# LVBarGraphDriver.net
KiCad netlist of a schematic drawn in EAGLE
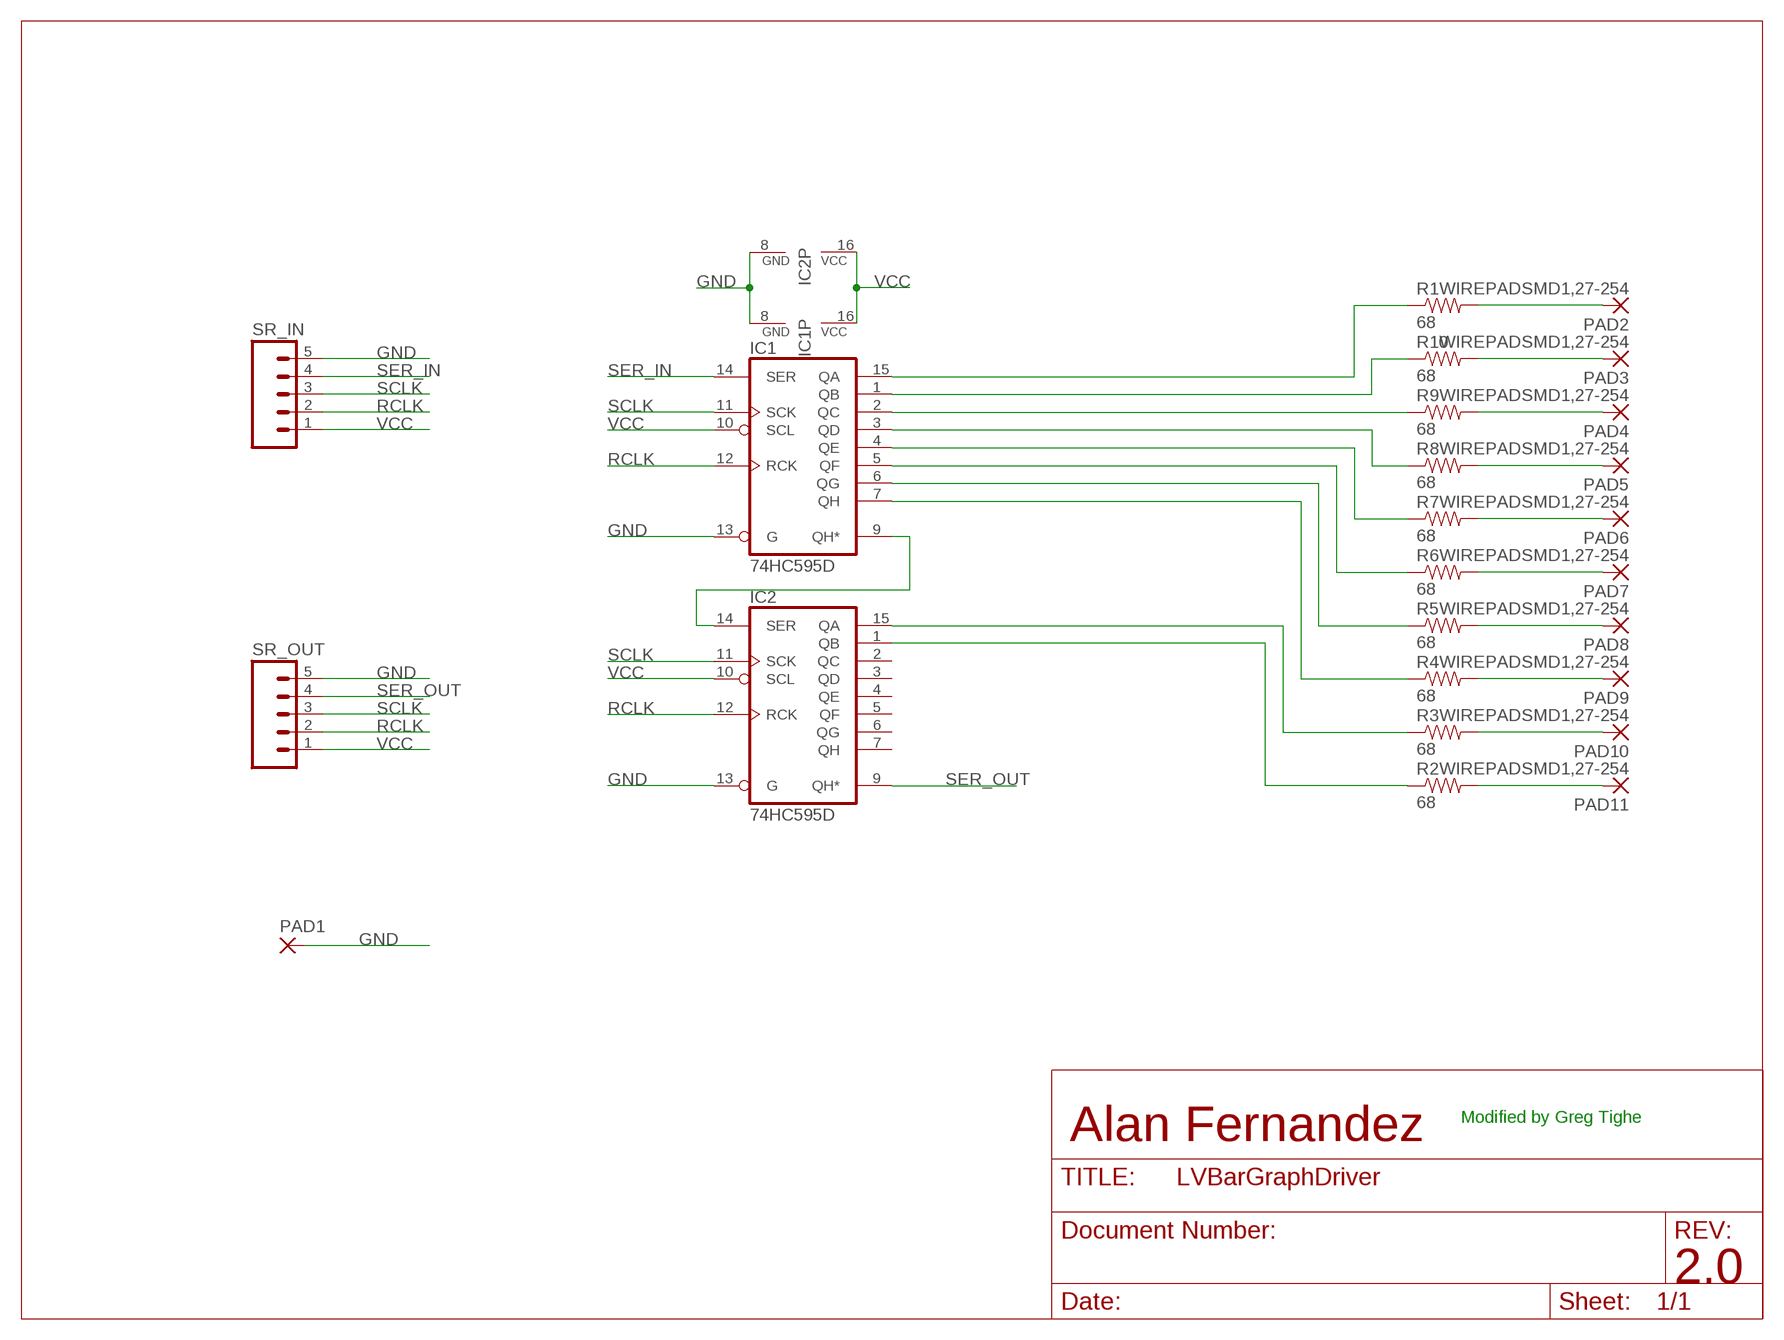
[diagram p0: schematic, sheet 1]

(export (version "E")
  (design (tool "Eeschema 10.0.6"))
  (components
    (comp (ref "IC1")
      (value "74HC595D")
      (footprint "eagle-import:SO16")
      (libsource (lib "eagle-import") (part "74595DHC"))
    )
    (comp (ref "IC2")
      (value "74HC595D")
      (footprint "eagle-import:SO16")
      (libsource (lib "eagle-import") (part "74595DHC"))
    )
    (comp (ref "PAD1")
      (value "SMD2")
      (footprint "eagle-import:SMD1,27-2,54")
      (libsource (lib "eagle-import") (part "SMD2"))
    )
    (comp (ref "PAD2")
      (value "WIREPADSMD1,27-254")
      (footprint "eagle-import:SMD1,27-2,54")
      (libsource (lib "eagle-import") (part "WIREPADSMD1,27-254"))
    )
    (comp (ref "PAD3")
      (value "WIREPADSMD1,27-254")
      (footprint "eagle-import:SMD1,27-2,54")
      (libsource (lib "eagle-import") (part "WIREPADSMD1,27-254"))
    )
    (comp (ref "PAD4")
      (value "WIREPADSMD1,27-254")
      (footprint "eagle-import:SMD1,27-2,54")
      (libsource (lib "eagle-import") (part "WIREPADSMD1,27-254"))
    )
    (comp (ref "PAD5")
      (value "WIREPADSMD1,27-254")
      (footprint "eagle-import:SMD1,27-2,54")
      (libsource (lib "eagle-import") (part "WIREPADSMD1,27-254"))
    )
    (comp (ref "PAD6")
      (value "WIREPADSMD1,27-254")
      (footprint "eagle-import:SMD1,27-2,54")
      (libsource (lib "eagle-import") (part "WIREPADSMD1,27-254"))
    )
    (comp (ref "PAD7")
      (value "WIREPADSMD1,27-254")
      (footprint "eagle-import:SMD1,27-2,54")
      (libsource (lib "eagle-import") (part "WIREPADSMD1,27-254"))
    )
    (comp (ref "PAD8")
      (value "WIREPADSMD1,27-254")
      (footprint "eagle-import:SMD1,27-2,54")
      (libsource (lib "eagle-import") (part "WIREPADSMD1,27-254"))
    )
    (comp (ref "PAD9")
      (value "WIREPADSMD1,27-254")
      (footprint "eagle-import:SMD1,27-2,54")
      (libsource (lib "eagle-import") (part "WIREPADSMD1,27-254"))
    )
    (comp (ref "PAD10")
      (value "WIREPADSMD1,27-254")
      (footprint "eagle-import:SMD1,27-2,54")
      (libsource (lib "eagle-import") (part "WIREPADSMD1,27-254"))
    )
    (comp (ref "PAD11")
      (value "WIREPADSMD1,27-254")
      (footprint "eagle-import:SMD1,27-2,54")
      (libsource (lib "eagle-import") (part "WIREPADSMD1,27-254"))
    )
    (comp (ref "R1")
      (value "68")
      (footprint "eagle-import:1206")
      (libsource (lib "eagle-import") (part "RESISTOR1206"))
    )
    (comp (ref "R2")
      (value "68")
      (footprint "eagle-import:1206")
      (libsource (lib "eagle-import") (part "RESISTOR1206"))
    )
    (comp (ref "R3")
      (value "68")
      (footprint "eagle-import:1206")
      (libsource (lib "eagle-import") (part "RESISTOR1206"))
    )
    (comp (ref "R4")
      (value "68")
      (footprint "eagle-import:1206")
      (libsource (lib "eagle-import") (part "RESISTOR1206"))
    )
    (comp (ref "R5")
      (value "68")
      (footprint "eagle-import:1206")
      (libsource (lib "eagle-import") (part "RESISTOR1206"))
    )
    (comp (ref "R6")
      (value "68")
      (footprint "eagle-import:1206")
      (libsource (lib "eagle-import") (part "RESISTOR1206"))
    )
    (comp (ref "R7")
      (value "68")
      (footprint "eagle-import:1206")
      (libsource (lib "eagle-import") (part "RESISTOR1206"))
    )
    (comp (ref "R8")
      (value "68")
      (footprint "eagle-import:1206")
      (libsource (lib "eagle-import") (part "RESISTOR1206"))
    )
    (comp (ref "R9")
      (value "68")
      (footprint "eagle-import:1206")
      (libsource (lib "eagle-import") (part "RESISTOR1206"))
    )
    (comp (ref "R10")
      (value "68")
      (footprint "eagle-import:1206")
      (libsource (lib "eagle-import") (part "RESISTOR1206"))
    )
    (comp (ref "SR_IN")
      (value "M05PTH")
      (footprint "eagle-import:1X05")
      (libsource (lib "eagle-import") (part "M05PTH"))
    )
    (comp (ref "SR_OUT")
      (value "M05PTH")
      (footprint "eagle-import:1X05")
      (libsource (lib "eagle-import") (part "M05PTH"))
    )
  )
  (nets
    (net (code "1") (name "/GND") (class "Default")
      (node (ref "IC1") (pin "13") (pinfunction "G_13") (pintype "input"))
      (node (ref "IC1") (pin "8") (pinfunction "GND_8") (pintype "power_in"))
      (node (ref "IC2") (pin "13") (pinfunction "G_13") (pintype "input"))
      (node (ref "IC2") (pin "8") (pinfunction "GND_8") (pintype "power_in"))
      (node (ref "PAD1") (pin "1") (pinfunction "P_1") (pintype "passive"))
      (node (ref "SR_IN") (pin "5") (pinfunction "5_5") (pintype "passive"))
      (node (ref "SR_OUT") (pin "5") (pinfunction "5_5") (pintype "passive"))
    )
    (net (code "2") (name "/RCLK") (class "Default")
      (node (ref "IC1") (pin "12") (pinfunction "RCK_12") (pintype "input"))
      (node (ref "IC2") (pin "12") (pinfunction "RCK_12") (pintype "input"))
      (node (ref "SR_IN") (pin "2") (pinfunction "2_2") (pintype "passive"))
      (node (ref "SR_OUT") (pin "2") (pinfunction "2_2") (pintype "passive"))
    )
    (net (code "3") (name "/SCLK") (class "Default")
      (node (ref "IC1") (pin "11") (pinfunction "SCK_11") (pintype "input"))
      (node (ref "IC2") (pin "11") (pinfunction "SCK_11") (pintype "input"))
      (node (ref "SR_IN") (pin "3") (pinfunction "3_3") (pintype "passive"))
      (node (ref "SR_OUT") (pin "3") (pinfunction "3_3") (pintype "passive"))
    )
    (net (code "4") (name "/SER_IN") (class "Default")
      (node (ref "IC1") (pin "14") (pinfunction "SER_14") (pintype "input"))
      (node (ref "SR_IN") (pin "4") (pinfunction "4_4") (pintype "passive"))
    )
    (net (code "5") (name "/SER_OUT") (class "Default")
      (node (ref "IC2") (pin "9") (pinfunction "QH*_9") (pintype "tri_state"))
      (node (ref "SR_OUT") (pin "4") (pinfunction "4_4") (pintype "passive"))
    )
    (net (code "6") (name "/VCC") (class "Default")
      (node (ref "IC1") (pin "10") (pinfunction "SCL_10") (pintype "input"))
      (node (ref "IC1") (pin "16") (pinfunction "VCC_16") (pintype "power_in"))
      (node (ref "IC2") (pin "10") (pinfunction "SCL_10") (pintype "input"))
      (node (ref "IC2") (pin "16") (pinfunction "VCC_16") (pintype "power_in"))
      (node (ref "SR_IN") (pin "1") (pinfunction "1_1") (pintype "passive"))
      (node (ref "SR_OUT") (pin "1") (pinfunction "1_1") (pintype "passive"))
    )
    (net (code "7") (name "Net-(IC1A-QA)") (class "Default")
      (node (ref "IC1") (pin "15") (pinfunction "QA_15") (pintype "tri_state"))
      (node (ref "R1") (pin "1") (pinfunction "1_1") (pintype "passive"))
    )
    (net (code "8") (name "Net-(IC1A-QB)") (class "Default")
      (node (ref "IC1") (pin "1") (pinfunction "QB_1") (pintype "tri_state"))
      (node (ref "R10") (pin "1") (pinfunction "1_1") (pintype "passive"))
    )
    (net (code "9") (name "Net-(IC1A-QC)") (class "Default")
      (node (ref "IC1") (pin "2") (pinfunction "QC_2") (pintype "tri_state"))
      (node (ref "R9") (pin "1") (pinfunction "1_1") (pintype "passive"))
    )
    (net (code "10") (name "Net-(IC1A-QD)") (class "Default")
      (node (ref "IC1") (pin "3") (pinfunction "QD_3") (pintype "tri_state"))
      (node (ref "R8") (pin "1") (pinfunction "1_1") (pintype "passive"))
    )
    (net (code "11") (name "Net-(IC1A-QE)") (class "Default")
      (node (ref "IC1") (pin "4") (pinfunction "QE_4") (pintype "tri_state"))
      (node (ref "R7") (pin "1") (pinfunction "1_1") (pintype "passive"))
    )
    (net (code "12") (name "Net-(IC1A-QF)") (class "Default")
      (node (ref "IC1") (pin "5") (pinfunction "QF_5") (pintype "tri_state"))
      (node (ref "R6") (pin "1") (pinfunction "1_1") (pintype "passive"))
    )
    (net (code "13") (name "Net-(IC1A-QG)") (class "Default")
      (node (ref "IC1") (pin "6") (pinfunction "QG_6") (pintype "tri_state"))
      (node (ref "R5") (pin "1") (pinfunction "1_1") (pintype "passive"))
    )
    (net (code "14") (name "Net-(IC1A-QH)") (class "Default")
      (node (ref "IC1") (pin "7") (pinfunction "QH_7") (pintype "tri_state"))
      (node (ref "R4") (pin "1") (pinfunction "1_1") (pintype "passive"))
    )
    (net (code "15") (name "Net-(IC1A-QH*)") (class "Default")
      (node (ref "IC1") (pin "9") (pinfunction "QH*_9") (pintype "tri_state"))
      (node (ref "IC2") (pin "14") (pinfunction "SER_14") (pintype "input"))
    )
    (net (code "16") (name "Net-(IC2A-QA)") (class "Default")
      (node (ref "IC2") (pin "15") (pinfunction "QA_15") (pintype "tri_state"))
      (node (ref "R3") (pin "1") (pinfunction "1_1") (pintype "passive"))
    )
    (net (code "17") (name "Net-(IC2A-QB)") (class "Default")
      (node (ref "IC2") (pin "1") (pinfunction "QB_1") (pintype "tri_state"))
      (node (ref "R2") (pin "1") (pinfunction "1_1") (pintype "passive"))
    )
    (net (code "18") (name "Net-(PAD2-P)") (class "Default")
      (node (ref "PAD2") (pin "1") (pinfunction "P_1") (pintype "passive"))
      (node (ref "R1") (pin "2") (pinfunction "2_2") (pintype "passive"))
    )
    (net (code "19") (name "Net-(PAD3-P)") (class "Default")
      (node (ref "PAD3") (pin "1") (pinfunction "P_1") (pintype "passive"))
      (node (ref "R10") (pin "2") (pinfunction "2_2") (pintype "passive"))
    )
    (net (code "20") (name "Net-(PAD4-P)") (class "Default")
      (node (ref "PAD4") (pin "1") (pinfunction "P_1") (pintype "passive"))
      (node (ref "R9") (pin "2") (pinfunction "2_2") (pintype "passive"))
    )
    (net (code "21") (name "Net-(PAD5-P)") (class "Default")
      (node (ref "PAD5") (pin "1") (pinfunction "P_1") (pintype "passive"))
      (node (ref "R8") (pin "2") (pinfunction "2_2") (pintype "passive"))
    )
    (net (code "22") (name "Net-(PAD6-P)") (class "Default")
      (node (ref "PAD6") (pin "1") (pinfunction "P_1") (pintype "passive"))
      (node (ref "R7") (pin "2") (pinfunction "2_2") (pintype "passive"))
    )
    (net (code "23") (name "Net-(PAD7-P)") (class "Default")
      (node (ref "PAD7") (pin "1") (pinfunction "P_1") (pintype "passive"))
      (node (ref "R6") (pin "2") (pinfunction "2_2") (pintype "passive"))
    )
    (net (code "24") (name "Net-(PAD8-P)") (class "Default")
      (node (ref "PAD8") (pin "1") (pinfunction "P_1") (pintype "passive"))
      (node (ref "R5") (pin "2") (pinfunction "2_2") (pintype "passive"))
    )
    (net (code "25") (name "Net-(PAD9-P)") (class "Default")
      (node (ref "PAD9") (pin "1") (pinfunction "P_1") (pintype "passive"))
      (node (ref "R4") (pin "2") (pinfunction "2_2") (pintype "passive"))
    )
    (net (code "26") (name "Net-(PAD10-P)") (class "Default")
      (node (ref "PAD10") (pin "1") (pinfunction "P_1") (pintype "passive"))
      (node (ref "R3") (pin "2") (pinfunction "2_2") (pintype "passive"))
    )
    (net (code "27") (name "Net-(PAD11-P)") (class "Default")
      (node (ref "PAD11") (pin "1") (pinfunction "P_1") (pintype "passive"))
      (node (ref "R2") (pin "2") (pinfunction "2_2") (pintype "passive"))
    )
    (net (code "28") (name "unconnected-(IC2A-QC-Pad2)") (class "Default")
      (node (ref "IC2") (pin "2") (pinfunction "QC_2") (pintype "tri_state"))
    )
    (net (code "29") (name "unconnected-(IC2A-QD-Pad3)") (class "Default")
      (node (ref "IC2") (pin "3") (pinfunction "QD_3") (pintype "tri_state"))
    )
    (net (code "30") (name "unconnected-(IC2A-QE-Pad4)") (class "Default")
      (node (ref "IC2") (pin "4") (pinfunction "QE_4") (pintype "tri_state"))
    )
    (net (code "31") (name "unconnected-(IC2A-QF-Pad5)") (class "Default")
      (node (ref "IC2") (pin "5") (pinfunction "QF_5") (pintype "tri_state"))
    )
    (net (code "32") (name "unconnected-(IC2A-QG-Pad6)") (class "Default")
      (node (ref "IC2") (pin "6") (pinfunction "QG_6") (pintype "tri_state"))
    )
    (net (code "33") (name "unconnected-(IC2A-QH-Pad7)") (class "Default")
      (node (ref "IC2") (pin "7") (pinfunction "QH_7") (pintype "tri_state"))
    )
  )
)
